# ShowMeShield.net
KiCad netlist of a schematic drawn in EAGLE
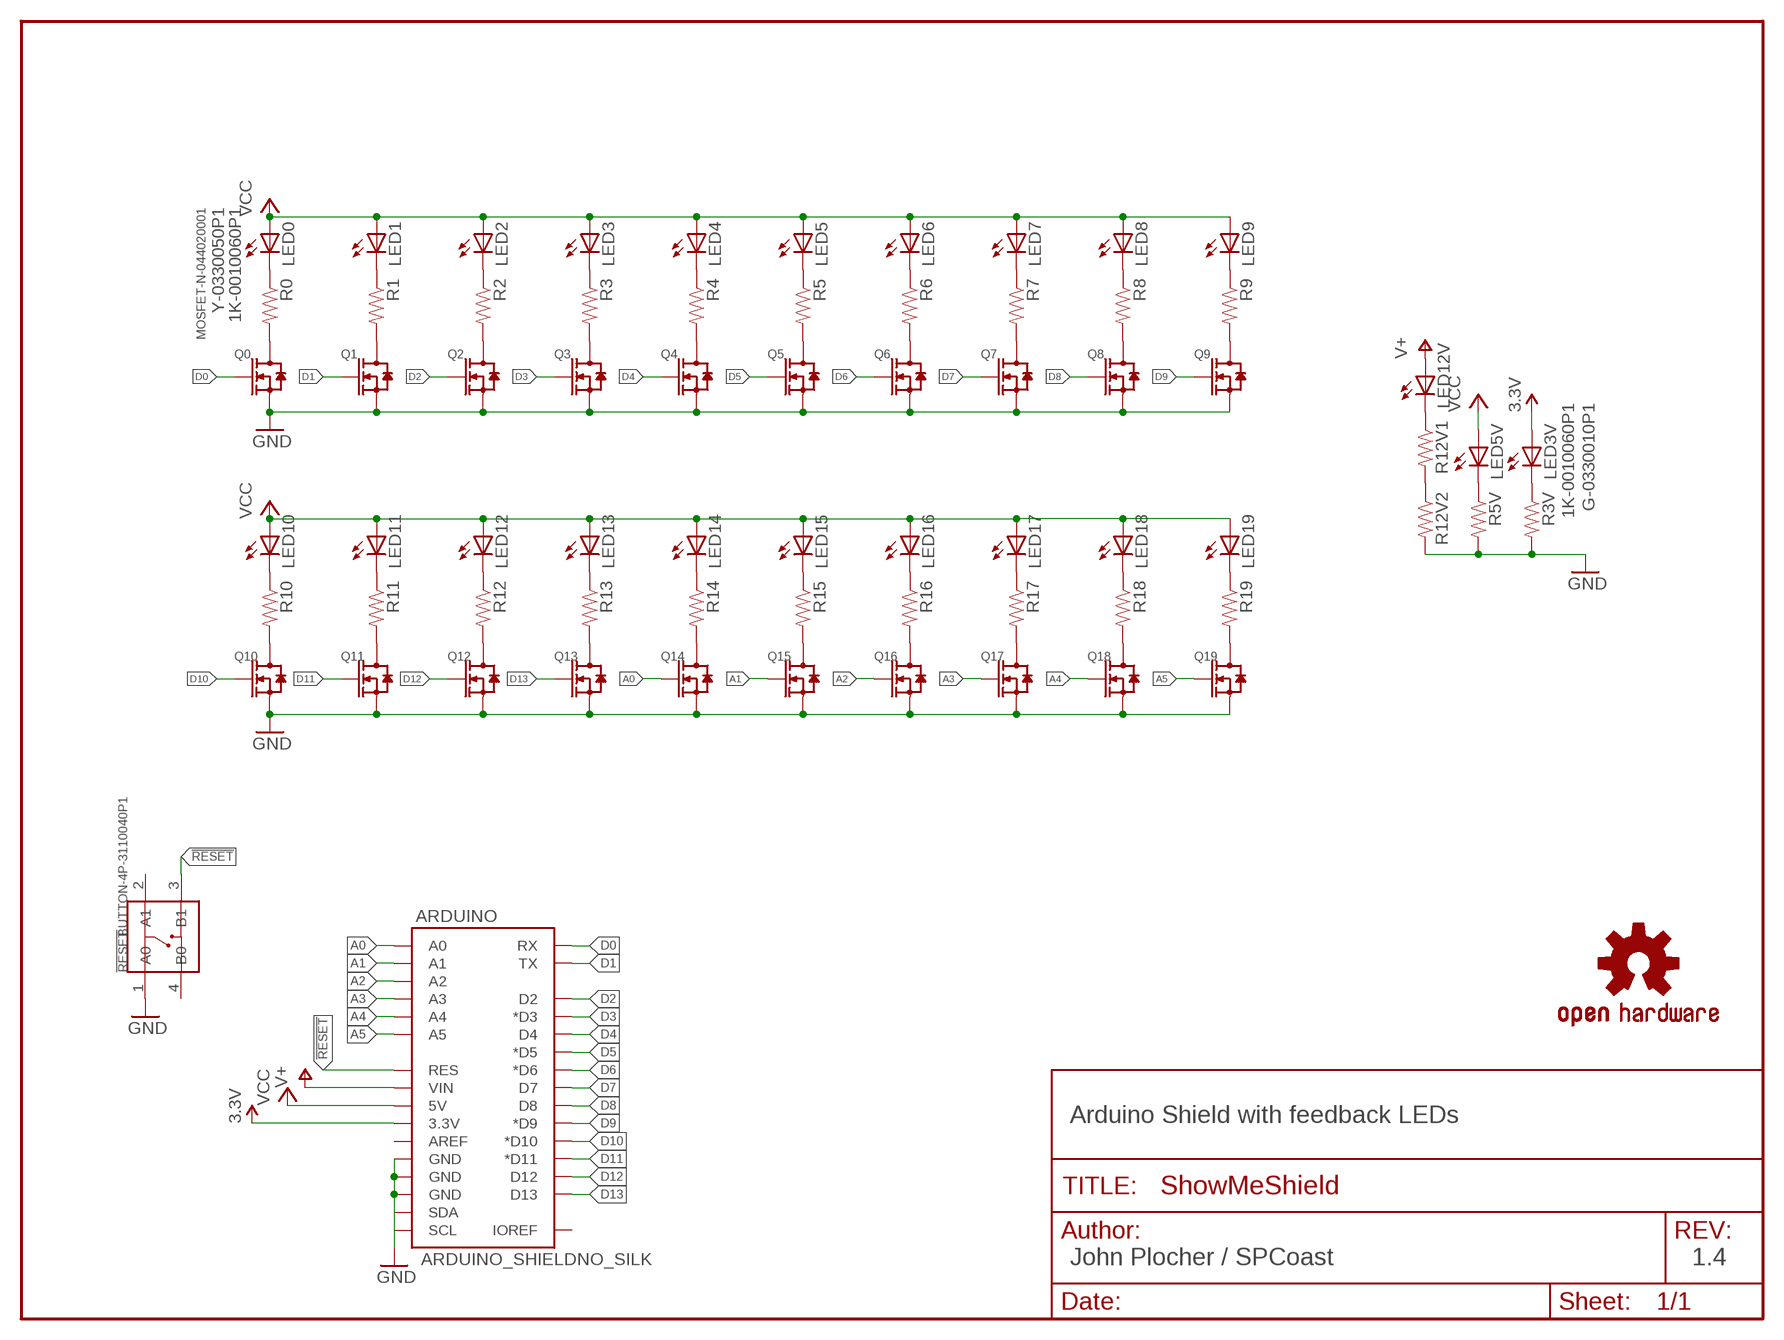
[diagram p0: schematic, sheet 1]

(export (version "E")
  (design (tool "Eeschema 10.0.6"))
  (components
    (comp (ref "!RESET")
      (value "BUTTON-4P-3110040P1")
      (footprint "eagle-import:4P-6.0X6.0X5.0H")
      (libsource (lib "eagle-import") (part "BUTTON-4P-3110040P1"))
    )
    (comp (ref "ARDUINO")
      (value "ARDUINO_SHIELDNO_SILK")
      (footprint "eagle-import:DUEMILANOVE_VIAS")
      (libsource (lib "eagle-import") (part "ARDUINO_SHIELDNO_SILK"))
    )
    (comp (ref "LED0")
      (value "Y-0330050P1")
      (footprint "eagle-import:CHIPLED_0603")
      (libsource (lib "eagle-import") (part "LEDCHIPLED_0603"))
    )
    (comp (ref "LED1")
      (value "Y-0330050P1")
      (footprint "eagle-import:CHIPLED_0603")
      (libsource (lib "eagle-import") (part "LEDCHIPLED_0603"))
    )
    (comp (ref "LED2")
      (value "Y-0330050P1")
      (footprint "eagle-import:CHIPLED_0603")
      (libsource (lib "eagle-import") (part "LEDCHIPLED_0603"))
    )
    (comp (ref "LED3")
      (value "Y-0330050P1")
      (footprint "eagle-import:CHIPLED_0603")
      (libsource (lib "eagle-import") (part "LEDCHIPLED_0603"))
    )
    (comp (ref "LED3V")
      (value "G-0330010P1")
      (footprint "eagle-import:CHIPLED_0603")
      (libsource (lib "eagle-import") (part "LEDCHIPLED_0603"))
    )
    (comp (ref "LED4")
      (value "Y-0330050P1")
      (footprint "eagle-import:CHIPLED_0603")
      (libsource (lib "eagle-import") (part "LEDCHIPLED_0603"))
    )
    (comp (ref "LED5")
      (value "Y-0330050P1")
      (footprint "eagle-import:CHIPLED_0603")
      (libsource (lib "eagle-import") (part "LEDCHIPLED_0603"))
    )
    (comp (ref "LED5V")
      (value "G-0330010P1")
      (footprint "eagle-import:CHIPLED_0603")
      (libsource (lib "eagle-import") (part "LEDCHIPLED_0603"))
    )
    (comp (ref "LED6")
      (value "Y-0330050P1")
      (footprint "eagle-import:CHIPLED_0603")
      (libsource (lib "eagle-import") (part "LEDCHIPLED_0603"))
    )
    (comp (ref "LED7")
      (value "Y-0330050P1")
      (footprint "eagle-import:CHIPLED_0603")
      (libsource (lib "eagle-import") (part "LEDCHIPLED_0603"))
    )
    (comp (ref "LED8")
      (value "Y-0330050P1")
      (footprint "eagle-import:CHIPLED_0603")
      (libsource (lib "eagle-import") (part "LEDCHIPLED_0603"))
    )
    (comp (ref "LED9")
      (value "Y-0330050P1")
      (footprint "eagle-import:CHIPLED_0603")
      (libsource (lib "eagle-import") (part "LEDCHIPLED_0603"))
    )
    (comp (ref "LED10")
      (value "Y-0330050P1")
      (footprint "eagle-import:CHIPLED_0603")
      (libsource (lib "eagle-import") (part "LEDCHIPLED_0603"))
    )
    (comp (ref "LED11")
      (value "Y-0330050P1")
      (footprint "eagle-import:CHIPLED_0603")
      (libsource (lib "eagle-import") (part "LEDCHIPLED_0603"))
    )
    (comp (ref "LED12")
      (value "Y-0330050P1")
      (footprint "eagle-import:CHIPLED_0603")
      (libsource (lib "eagle-import") (part "LEDCHIPLED_0603"))
    )
    (comp (ref "LED12V")
      (value "G-0330010P1")
      (footprint "eagle-import:CHIPLED_0603")
      (libsource (lib "eagle-import") (part "LEDCHIPLED_0603"))
    )
    (comp (ref "LED13")
      (value "Y-0330050P1")
      (footprint "eagle-import:CHIPLED_0603")
      (libsource (lib "eagle-import") (part "LEDCHIPLED_0603"))
    )
    (comp (ref "LED14")
      (value "Y-0330050P1")
      (footprint "eagle-import:CHIPLED_0603")
      (libsource (lib "eagle-import") (part "LEDCHIPLED_0603"))
    )
    (comp (ref "LED15")
      (value "Y-0330050P1")
      (footprint "eagle-import:CHIPLED_0603")
      (libsource (lib "eagle-import") (part "LEDCHIPLED_0603"))
    )
    (comp (ref "LED16")
      (value "Y-0330050P1")
      (footprint "eagle-import:CHIPLED_0603")
      (libsource (lib "eagle-import") (part "LEDCHIPLED_0603"))
    )
    (comp (ref "LED17")
      (value "Y-0330050P1")
      (footprint "eagle-import:CHIPLED_0603")
      (libsource (lib "eagle-import") (part "LEDCHIPLED_0603"))
    )
    (comp (ref "LED18")
      (value "Y-0330050P1")
      (footprint "eagle-import:CHIPLED_0603")
      (libsource (lib "eagle-import") (part "LEDCHIPLED_0603"))
    )
    (comp (ref "LED19")
      (value "Y-0330050P1")
      (footprint "eagle-import:CHIPLED_0603")
      (libsource (lib "eagle-import") (part "LEDCHIPLED_0603"))
    )
    (comp (ref "Q0")
      (value "MOSFET-N-044020001")
      (footprint "eagle-import:SOT23")
      (libsource (lib "eagle-import") (part "MOSFET-N-044020001"))
    )
    (comp (ref "Q1")
      (value "MOSFET-N-044020001")
      (footprint "eagle-import:SOT23")
      (libsource (lib "eagle-import") (part "MOSFET-N-044020001"))
    )
    (comp (ref "Q2")
      (value "MOSFET-N-044020001")
      (footprint "eagle-import:SOT23")
      (libsource (lib "eagle-import") (part "MOSFET-N-044020001"))
    )
    (comp (ref "Q3")
      (value "MOSFET-N-044020001")
      (footprint "eagle-import:SOT23")
      (libsource (lib "eagle-import") (part "MOSFET-N-044020001"))
    )
    (comp (ref "Q4")
      (value "MOSFET-N-044020001")
      (footprint "eagle-import:SOT23")
      (libsource (lib "eagle-import") (part "MOSFET-N-044020001"))
    )
    (comp (ref "Q5")
      (value "MOSFET-N-044020001")
      (footprint "eagle-import:SOT23")
      (libsource (lib "eagle-import") (part "MOSFET-N-044020001"))
    )
    (comp (ref "Q6")
      (value "MOSFET-N-044020001")
      (footprint "eagle-import:SOT23")
      (libsource (lib "eagle-import") (part "MOSFET-N-044020001"))
    )
    (comp (ref "Q7")
      (value "MOSFET-N-044020001")
      (footprint "eagle-import:SOT23")
      (libsource (lib "eagle-import") (part "MOSFET-N-044020001"))
    )
    (comp (ref "Q8")
      (value "MOSFET-N-044020001")
      (footprint "eagle-import:SOT23")
      (libsource (lib "eagle-import") (part "MOSFET-N-044020001"))
    )
    (comp (ref "Q9")
      (value "MOSFET-N-044020001")
      (footprint "eagle-import:SOT23")
      (libsource (lib "eagle-import") (part "MOSFET-N-044020001"))
    )
    (comp (ref "Q10")
      (value "MOSFET-N-044020001")
      (footprint "eagle-import:SOT23")
      (libsource (lib "eagle-import") (part "MOSFET-N-044020001"))
    )
    (comp (ref "Q11")
      (value "MOSFET-N-044020001")
      (footprint "eagle-import:SOT23")
      (libsource (lib "eagle-import") (part "MOSFET-N-044020001"))
    )
    (comp (ref "Q12")
      (value "MOSFET-N-044020001")
      (footprint "eagle-import:SOT23")
      (libsource (lib "eagle-import") (part "MOSFET-N-044020001"))
    )
    (comp (ref "Q13")
      (value "MOSFET-N-044020001")
      (footprint "eagle-import:SOT23")
      (libsource (lib "eagle-import") (part "MOSFET-N-044020001"))
    )
    (comp (ref "Q14")
      (value "MOSFET-N-044020001")
      (footprint "eagle-import:SOT23")
      (libsource (lib "eagle-import") (part "MOSFET-N-044020001"))
    )
    (comp (ref "Q15")
      (value "MOSFET-N-044020001")
      (footprint "eagle-import:SOT23")
      (libsource (lib "eagle-import") (part "MOSFET-N-044020001"))
    )
    (comp (ref "Q16")
      (value "MOSFET-N-044020001")
      (footprint "eagle-import:SOT23")
      (libsource (lib "eagle-import") (part "MOSFET-N-044020001"))
    )
    (comp (ref "Q17")
      (value "MOSFET-N-044020001")
      (footprint "eagle-import:SOT23")
      (libsource (lib "eagle-import") (part "MOSFET-N-044020001"))
    )
    (comp (ref "Q18")
      (value "MOSFET-N-044020001")
      (footprint "eagle-import:SOT23")
      (libsource (lib "eagle-import") (part "MOSFET-N-044020001"))
    )
    (comp (ref "Q19")
      (value "MOSFET-N-044020001")
      (footprint "eagle-import:SOT23")
      (libsource (lib "eagle-import") (part "MOSFET-N-044020001"))
    )
    (comp (ref "R0")
      (value "1K-0010060P1")
      (footprint "eagle-import:0603-RES")
      (libsource (lib "eagle-import") (part "RESISTOR0603-RES"))
    )
    (comp (ref "R1")
      (value "1K-0010060P1")
      (footprint "eagle-import:0603-RES")
      (libsource (lib "eagle-import") (part "RESISTOR0603-RES"))
    )
    (comp (ref "R2")
      (value "1K-0010060P1")
      (footprint "eagle-import:0603-RES")
      (libsource (lib "eagle-import") (part "RESISTOR0603-RES"))
    )
    (comp (ref "R3")
      (value "1K-0010060P1")
      (footprint "eagle-import:0603-RES")
      (libsource (lib "eagle-import") (part "RESISTOR0603-RES"))
    )
    (comp (ref "R3V")
      (value "1K-0010060P1")
      (footprint "eagle-import:0603-RES")
      (libsource (lib "eagle-import") (part "RESISTOR0603-RES"))
    )
    (comp (ref "R4")
      (value "1K-0010060P1")
      (footprint "eagle-import:0603-RES")
      (libsource (lib "eagle-import") (part "RESISTOR0603-RES"))
    )
    (comp (ref "R5")
      (value "1K-0010060P1")
      (footprint "eagle-import:0603-RES")
      (libsource (lib "eagle-import") (part "RESISTOR0603-RES"))
    )
    (comp (ref "R5V")
      (value "1K-0010060P1")
      (footprint "eagle-import:0603-RES")
      (libsource (lib "eagle-import") (part "RESISTOR0603-RES"))
    )
    (comp (ref "R6")
      (value "1K-0010060P1")
      (footprint "eagle-import:0603-RES")
      (libsource (lib "eagle-import") (part "RESISTOR0603-RES"))
    )
    (comp (ref "R7")
      (value "1K-0010060P1")
      (footprint "eagle-import:0603-RES")
      (libsource (lib "eagle-import") (part "RESISTOR0603-RES"))
    )
    (comp (ref "R8")
      (value "1K-0010060P1")
      (footprint "eagle-import:0603-RES")
      (libsource (lib "eagle-import") (part "RESISTOR0603-RES"))
    )
    (comp (ref "R9")
      (value "1K-0010060P1")
      (footprint "eagle-import:0603-RES")
      (libsource (lib "eagle-import") (part "RESISTOR0603-RES"))
    )
    (comp (ref "R10")
      (value "1K-0010060P1")
      (footprint "eagle-import:0603-RES")
      (libsource (lib "eagle-import") (part "RESISTOR0603-RES"))
    )
    (comp (ref "R11")
      (value "1K-0010060P1")
      (footprint "eagle-import:0603-RES")
      (libsource (lib "eagle-import") (part "RESISTOR0603-RES"))
    )
    (comp (ref "R12")
      (value "1K-0010060P1")
      (footprint "eagle-import:0603-RES")
      (libsource (lib "eagle-import") (part "RESISTOR0603-RES"))
    )
    (comp (ref "R12V1")
      (value "1K-0010060P1")
      (footprint "eagle-import:0603-RES")
      (libsource (lib "eagle-import") (part "RESISTOR0603-RES"))
    )
    (comp (ref "R12V2")
      (value "1K-0010060P1")
      (footprint "eagle-import:0603-RES")
      (libsource (lib "eagle-import") (part "RESISTOR0603-RES"))
    )
    (comp (ref "R13")
      (value "1K-0010060P1")
      (footprint "eagle-import:0603-RES")
      (libsource (lib "eagle-import") (part "RESISTOR0603-RES"))
    )
    (comp (ref "R14")
      (value "1K-0010060P1")
      (footprint "eagle-import:0603-RES")
      (libsource (lib "eagle-import") (part "RESISTOR0603-RES"))
    )
    (comp (ref "R15")
      (value "1K-0010060P1")
      (footprint "eagle-import:0603-RES")
      (libsource (lib "eagle-import") (part "RESISTOR0603-RES"))
    )
    (comp (ref "R16")
      (value "1K-0010060P1")
      (footprint "eagle-import:0603-RES")
      (libsource (lib "eagle-import") (part "RESISTOR0603-RES"))
    )
    (comp (ref "R17")
      (value "1K-0010060P1")
      (footprint "eagle-import:0603-RES")
      (libsource (lib "eagle-import") (part "RESISTOR0603-RES"))
    )
    (comp (ref "R18")
      (value "1K-0010060P1")
      (footprint "eagle-import:0603-RES")
      (libsource (lib "eagle-import") (part "RESISTOR0603-RES"))
    )
    (comp (ref "R19")
      (value "1K-0010060P1")
      (footprint "eagle-import:0603-RES")
      (libsource (lib "eagle-import") (part "RESISTOR0603-RES"))
    )
    (comp (ref "U$1")
      (value "OSHW-LOGOM")
      (footprint "eagle-import:OSHW-LOGO-M")
      (libsource (lib "eagle-import") (part "OSHW-LOGOM"))
    )
  )
  (nets
    (net (code "1") (name "/~{RESET}") (class "Default")
      (node (ref "!RESET") (pin "3") (pinfunction "B1_3") (pintype "bidirectional"))
      (node (ref "ARDUINO") (pin "RES") (pinfunction "RES_RES") (pintype "bidirectional"))
    )
    (net (code "2") (name "3.3V") (class "Default")
      (node (ref "ARDUINO") (pin "3.3V") (pinfunction "3.3V_3.3V") (pintype "bidirectional"))
      (node (ref "LED3V") (pin "A") (pinfunction "A_A") (pintype "passive"))
    )
    (net (code "3") (name "A0") (class "Default")
      (node (ref "ARDUINO") (pin "A0") (pinfunction "A0_A0") (pintype "bidirectional"))
      (node (ref "Q14") (pin "1") (pinfunction "G_1") (pintype "passive"))
    )
    (net (code "4") (name "A1") (class "Default")
      (node (ref "ARDUINO") (pin "A1") (pinfunction "A1_A1") (pintype "bidirectional"))
      (node (ref "Q15") (pin "1") (pinfunction "G_1") (pintype "passive"))
    )
    (net (code "5") (name "A2") (class "Default")
      (node (ref "ARDUINO") (pin "A2") (pinfunction "A2_A2") (pintype "bidirectional"))
      (node (ref "Q16") (pin "1") (pinfunction "G_1") (pintype "passive"))
    )
    (net (code "6") (name "A3") (class "Default")
      (node (ref "ARDUINO") (pin "A3") (pinfunction "A3_A3") (pintype "bidirectional"))
      (node (ref "Q17") (pin "1") (pinfunction "G_1") (pintype "passive"))
    )
    (net (code "7") (name "A4") (class "Default")
      (node (ref "ARDUINO") (pin "A4") (pinfunction "A4_A4") (pintype "bidirectional"))
      (node (ref "Q18") (pin "1") (pinfunction "G_1") (pintype "passive"))
    )
    (net (code "8") (name "A5") (class "Default")
      (node (ref "ARDUINO") (pin "A5") (pinfunction "A5_A5") (pintype "bidirectional"))
      (node (ref "Q19") (pin "1") (pinfunction "G_1") (pintype "passive"))
    )
    (net (code "9") (name "D0") (class "Default")
      (node (ref "ARDUINO") (pin "RX") (pinfunction "RX_RX") (pintype "bidirectional"))
      (node (ref "Q0") (pin "1") (pinfunction "G_1") (pintype "passive"))
    )
    (net (code "10") (name "D1") (class "Default")
      (node (ref "ARDUINO") (pin "TX") (pinfunction "TX_TX") (pintype "bidirectional"))
      (node (ref "Q1") (pin "1") (pinfunction "G_1") (pintype "passive"))
    )
    (net (code "11") (name "D2") (class "Default")
      (node (ref "ARDUINO") (pin "D2") (pinfunction "D2_D2") (pintype "bidirectional"))
      (node (ref "Q2") (pin "1") (pinfunction "G_1") (pintype "passive"))
    )
    (net (code "12") (name "D3") (class "Default")
      (node (ref "ARDUINO") (pin "D3") (pinfunction "*D3_D3") (pintype "bidirectional"))
      (node (ref "Q3") (pin "1") (pinfunction "G_1") (pintype "passive"))
    )
    (net (code "13") (name "D4") (class "Default")
      (node (ref "ARDUINO") (pin "D4") (pinfunction "D4_D4") (pintype "bidirectional"))
      (node (ref "Q4") (pin "1") (pinfunction "G_1") (pintype "passive"))
    )
    (net (code "14") (name "D5") (class "Default")
      (node (ref "ARDUINO") (pin "D5") (pinfunction "*D5_D5") (pintype "bidirectional"))
      (node (ref "Q5") (pin "1") (pinfunction "G_1") (pintype "passive"))
    )
    (net (code "15") (name "D6") (class "Default")
      (node (ref "ARDUINO") (pin "D6") (pinfunction "*D6_D6") (pintype "bidirectional"))
      (node (ref "Q6") (pin "1") (pinfunction "G_1") (pintype "passive"))
    )
    (net (code "16") (name "D7") (class "Default")
      (node (ref "ARDUINO") (pin "D7") (pinfunction "D7_D7") (pintype "bidirectional"))
      (node (ref "Q7") (pin "1") (pinfunction "G_1") (pintype "passive"))
    )
    (net (code "17") (name "D8") (class "Default")
      (node (ref "ARDUINO") (pin "D8") (pinfunction "D8_D8") (pintype "bidirectional"))
      (node (ref "Q8") (pin "1") (pinfunction "G_1") (pintype "passive"))
    )
    (net (code "18") (name "D9") (class "Default")
      (node (ref "ARDUINO") (pin "D9") (pinfunction "*D9_D9") (pintype "bidirectional"))
      (node (ref "Q9") (pin "1") (pinfunction "G_1") (pintype "passive"))
    )
    (net (code "19") (name "D10") (class "Default")
      (node (ref "ARDUINO") (pin "D10") (pinfunction "*D10_D10") (pintype "bidirectional"))
      (node (ref "Q10") (pin "1") (pinfunction "G_1") (pintype "passive"))
    )
    (net (code "20") (name "D11") (class "Default")
      (node (ref "ARDUINO") (pin "D11") (pinfunction "*D11_D11") (pintype "bidirectional"))
      (node (ref "Q11") (pin "1") (pinfunction "G_1") (pintype "passive"))
    )
    (net (code "21") (name "D12") (class "Default")
      (node (ref "ARDUINO") (pin "D12") (pinfunction "D12_D12") (pintype "bidirectional"))
      (node (ref "Q12") (pin "1") (pinfunction "G_1") (pintype "passive"))
    )
    (net (code "22") (name "D13") (class "Default")
      (node (ref "ARDUINO") (pin "D13") (pinfunction "D13_D13") (pintype "bidirectional"))
      (node (ref "Q13") (pin "1") (pinfunction "G_1") (pintype "passive"))
    )
    (net (code "23") (name "GND") (class "Default")
      (node (ref "!RESET") (pin "1") (pinfunction "A0_1") (pintype "bidirectional"))
      (node (ref "ARDUINO") (pin "GND@0") (pinfunction "GND_GND@0") (pintype "bidirectional"))
      (node (ref "ARDUINO") (pin "GND@1") (pinfunction "GND_GND@1") (pintype "bidirectional"))
      (node (ref "ARDUINO") (pin "GND@2") (pinfunction "GND_GND@2") (pintype "bidirectional"))
      (node (ref "Q0") (pin "2") (pinfunction "S_2") (pintype "passive"))
      (node (ref "Q1") (pin "2") (pinfunction "S_2") (pintype "passive"))
      (node (ref "Q10") (pin "2") (pinfunction "S_2") (pintype "passive"))
      (node (ref "Q11") (pin "2") (pinfunction "S_2") (pintype "passive"))
      (node (ref "Q12") (pin "2") (pinfunction "S_2") (pintype "passive"))
      (node (ref "Q13") (pin "2") (pinfunction "S_2") (pintype "passive"))
      (node (ref "Q14") (pin "2") (pinfunction "S_2") (pintype "passive"))
      (node (ref "Q15") (pin "2") (pinfunction "S_2") (pintype "passive"))
      (node (ref "Q16") (pin "2") (pinfunction "S_2") (pintype "passive"))
      (node (ref "Q17") (pin "2") (pinfunction "S_2") (pintype "passive"))
      (node (ref "Q18") (pin "2") (pinfunction "S_2") (pintype "passive"))
      (node (ref "Q19") (pin "2") (pinfunction "S_2") (pintype "passive"))
      (node (ref "Q2") (pin "2") (pinfunction "S_2") (pintype "passive"))
      (node (ref "Q3") (pin "2") (pinfunction "S_2") (pintype "passive"))
      (node (ref "Q4") (pin "2") (pinfunction "S_2") (pintype "passive"))
      (node (ref "Q5") (pin "2") (pinfunction "S_2") (pintype "passive"))
      (node (ref "Q6") (pin "2") (pinfunction "S_2") (pintype "passive"))
      (node (ref "Q7") (pin "2") (pinfunction "S_2") (pintype "passive"))
      (node (ref "Q8") (pin "2") (pinfunction "S_2") (pintype "passive"))
      (node (ref "Q9") (pin "2") (pinfunction "S_2") (pintype "passive"))
      (node (ref "R12V2") (pin "2") (pinfunction "2_2") (pintype "passive"))
      (node (ref "R3V") (pin "2") (pinfunction "2_2") (pintype "passive"))
      (node (ref "R5V") (pin "2") (pinfunction "2_2") (pintype "passive"))
    )
    (net (code "24") (name "Net-(LED0-PadC)") (class "Default")
      (node (ref "LED0") (pin "C") (pinfunction "C_C") (pintype "passive"))
      (node (ref "R0") (pin "1") (pinfunction "1_1") (pintype "passive"))
    )
    (net (code "25") (name "Net-(LED1-PadC)") (class "Default")
      (node (ref "LED1") (pin "C") (pinfunction "C_C") (pintype "passive"))
      (node (ref "R1") (pin "1") (pinfunction "1_1") (pintype "passive"))
    )
    (net (code "26") (name "Net-(LED2-PadC)") (class "Default")
      (node (ref "LED2") (pin "C") (pinfunction "C_C") (pintype "passive"))
      (node (ref "R2") (pin "1") (pinfunction "1_1") (pintype "passive"))
    )
    (net (code "27") (name "Net-(LED3-PadC)") (class "Default")
      (node (ref "LED3") (pin "C") (pinfunction "C_C") (pintype "passive"))
      (node (ref "R3") (pin "1") (pinfunction "1_1") (pintype "passive"))
    )
    (net (code "28") (name "Net-(LED3V-PadC)") (class "Default")
      (node (ref "LED3V") (pin "C") (pinfunction "C_C") (pintype "passive"))
      (node (ref "R3V") (pin "1") (pinfunction "1_1") (pintype "passive"))
    )
    (net (code "29") (name "Net-(LED4-PadC)") (class "Default")
      (node (ref "LED4") (pin "C") (pinfunction "C_C") (pintype "passive"))
      (node (ref "R4") (pin "1") (pinfunction "1_1") (pintype "passive"))
    )
    (net (code "30") (name "Net-(LED5-PadC)") (class "Default")
      (node (ref "LED5") (pin "C") (pinfunction "C_C") (pintype "passive"))
      (node (ref "R5") (pin "1") (pinfunction "1_1") (pintype "passive"))
    )
    (net (code "31") (name "Net-(LED5V-PadC)") (class "Default")
      (node (ref "LED5V") (pin "C") (pinfunction "C_C") (pintype "passive"))
      (node (ref "R5V") (pin "1") (pinfunction "1_1") (pintype "passive"))
    )
    (net (code "32") (name "Net-(LED6-PadC)") (class "Default")
      (node (ref "LED6") (pin "C") (pinfunction "C_C") (pintype "passive"))
      (node (ref "R6") (pin "1") (pinfunction "1_1") (pintype "passive"))
    )
    (net (code "33") (name "Net-(LED7-PadC)") (class "Default")
      (node (ref "LED7") (pin "C") (pinfunction "C_C") (pintype "passive"))
      (node (ref "R7") (pin "1") (pinfunction "1_1") (pintype "passive"))
    )
    (net (code "34") (name "Net-(LED8-PadC)") (class "Default")
      (node (ref "LED8") (pin "C") (pinfunction "C_C") (pintype "passive"))
      (node (ref "R8") (pin "1") (pinfunction "1_1") (pintype "passive"))
    )
    (net (code "35") (name "Net-(LED9-PadC)") (class "Default")
      (node (ref "LED9") (pin "C") (pinfunction "C_C") (pintype "passive"))
      (node (ref "R9") (pin "1") (pinfunction "1_1") (pintype "passive"))
    )
    (net (code "36") (name "Net-(LED10-PadC)") (class "Default")
      (node (ref "LED10") (pin "C") (pinfunction "C_C") (pintype "passive"))
      (node (ref "R10") (pin "1") (pinfunction "1_1") (pintype "passive"))
    )
    (net (code "37") (name "Net-(LED11-PadC)") (class "Default")
      (node (ref "LED11") (pin "C") (pinfunction "C_C") (pintype "passive"))
      (node (ref "R11") (pin "1") (pinfunction "1_1") (pintype "passive"))
    )
    (net (code "38") (name "Net-(LED12-PadC)") (class "Default")
      (node (ref "LED12") (pin "C") (pinfunction "C_C") (pintype "passive"))
      (node (ref "R12") (pin "1") (pinfunction "1_1") (pintype "passive"))
    )
    (net (code "39") (name "Net-(LED12V-PadC)") (class "Default")
      (node (ref "LED12V") (pin "C") (pinfunction "C_C") (pintype "passive"))
      (node (ref "R12V1") (pin "1") (pinfunction "1_1") (pintype "passive"))
    )
    (net (code "40") (name "Net-(LED13-PadC)") (class "Default")
      (node (ref "LED13") (pin "C") (pinfunction "C_C") (pintype "passive"))
      (node (ref "R13") (pin "1") (pinfunction "1_1") (pintype "passive"))
    )
    (net (code "41") (name "Net-(LED14-PadC)") (class "Default")
      (node (ref "LED14") (pin "C") (pinfunction "C_C") (pintype "passive"))
      (node (ref "R14") (pin "1") (pinfunction "1_1") (pintype "passive"))
    )
    (net (code "42") (name "Net-(LED15-PadC)") (class "Default")
      (node (ref "LED15") (pin "C") (pinfunction "C_C") (pintype "passive"))
      (node (ref "R15") (pin "1") (pinfunction "1_1") (pintype "passive"))
    )
    (net (code "43") (name "Net-(LED16-PadC)") (class "Default")
      (node (ref "LED16") (pin "C") (pinfunction "C_C") (pintype "passive"))
      (node (ref "R16") (pin "1") (pinfunction "1_1") (pintype "passive"))
    )
    (net (code "44") (name "Net-(LED17-PadC)") (class "Default")
      (node (ref "LED17") (pin "C") (pinfunction "C_C") (pintype "passive"))
      (node (ref "R17") (pin "1") (pinfunction "1_1") (pintype "passive"))
    )
    (net (code "45") (name "Net-(LED18-PadC)") (class "Default")
      (node (ref "LED18") (pin "C") (pinfunction "C_C") (pintype "passive"))
      (node (ref "R18") (pin "1") (pinfunction "1_1") (pintype "passive"))
    )
    (net (code "46") (name "Net-(LED19-PadC)") (class "Default")
      (node (ref "LED19") (pin "C") (pinfunction "C_C") (pintype "passive"))
      (node (ref "R19") (pin "1") (pinfunction "1_1") (pintype "passive"))
    )
    (net (code "47") (name "Net-(Q0-D)") (class "Default")
      (node (ref "Q0") (pin "3") (pinfunction "D_3") (pintype "passive"))
      (node (ref "R0") (pin "2") (pinfunction "2_2") (pintype "passive"))
    )
    (net (code "48") (name "Net-(Q1-D)") (class "Default")
      (node (ref "Q1") (pin "3") (pinfunction "D_3") (pintype "passive"))
      (node (ref "R1") (pin "2") (pinfunction "2_2") (pintype "passive"))
    )
    (net (code "49") (name "Net-(Q2-D)") (class "Default")
      (node (ref "Q2") (pin "3") (pinfunction "D_3") (pintype "passive"))
      (node (ref "R2") (pin "2") (pinfunction "2_2") (pintype "passive"))
    )
    (net (code "50") (name "Net-(Q3-D)") (class "Default")
      (node (ref "Q3") (pin "3") (pinfunction "D_3") (pintype "passive"))
      (node (ref "R3") (pin "2") (pinfunction "2_2") (pintype "passive"))
    )
    (net (code "51") (name "Net-(Q4-D)") (class "Default")
      (node (ref "Q4") (pin "3") (pinfunction "D_3") (pintype "passive"))
      (node (ref "R4") (pin "2") (pinfunction "2_2") (pintype "passive"))
    )
    (net (code "52") (name "Net-(Q5-D)") (class "Default")
      (node (ref "Q5") (pin "3") (pinfunction "D_3") (pintype "passive"))
      (node (ref "R5") (pin "2") (pinfunction "2_2") (pintype "passive"))
    )
    (net (code "53") (name "Net-(Q6-D)") (class "Default")
      (node (ref "Q6") (pin "3") (pinfunction "D_3") (pintype "passive"))
      (node (ref "R6") (pin "2") (pinfunction "2_2") (pintype "passive"))
    )
    (net (code "54") (name "Net-(Q7-D)") (class "Default")
      (node (ref "Q7") (pin "3") (pinfunction "D_3") (pintype "passive"))
      (node (ref "R7") (pin "2") (pinfunction "2_2") (pintype "passive"))
    )
    (net (code "55") (name "Net-(Q8-D)") (class "Default")
      (node (ref "Q8") (pin "3") (pinfunction "D_3") (pintype "passive"))
      (node (ref "R8") (pin "2") (pinfunction "2_2") (pintype "passive"))
    )
    (net (code "56") (name "Net-(Q9-D)") (class "Default")
      (node (ref "Q9") (pin "3") (pinfunction "D_3") (pintype "passive"))
      (node (ref "R9") (pin "2") (pinfunction "2_2") (pintype "passive"))
    )
    (net (code "57") (name "Net-(Q10-D)") (class "Default")
      (node (ref "Q10") (pin "3") (pinfunction "D_3") (pintype "passive"))
      (node (ref "R10") (pin "2") (pinfunction "2_2") (pintype "passive"))
    )
    (net (code "58") (name "Net-(Q11-D)") (class "Default")
      (node (ref "Q11") (pin "3") (pinfunction "D_3") (pintype "passive"))
      (node (ref "R11") (pin "2") (pinfunction "2_2") (pintype "passive"))
    )
    (net (code "59") (name "Net-(Q12-D)") (class "Default")
      (node (ref "Q12") (pin "3") (pinfunction "D_3") (pintype "passive"))
      (node (ref "R12") (pin "2") (pinfunction "2_2") (pintype "passive"))
    )
    (net (code "60") (name "Net-(Q13-D)") (class "Default")
      (node (ref "Q13") (pin "3") (pinfunction "D_3") (pintype "passive"))
      (node (ref "R13") (pin "2") (pinfunction "2_2") (pintype "passive"))
    )
    (net (code "61") (name "Net-(Q14-D)") (class "Default")
      (node (ref "Q14") (pin "3") (pinfunction "D_3") (pintype "passive"))
      (node (ref "R14") (pin "2") (pinfunction "2_2") (pintype "passive"))
    )
    (net (code "62") (name "Net-(Q15-D)") (class "Default")
      (node (ref "Q15") (pin "3") (pinfunction "D_3") (pintype "passive"))
      (node (ref "R15") (pin "2") (pinfunction "2_2") (pintype "passive"))
    )
    (net (code "63") (name "Net-(Q16-D)") (class "Default")
      (node (ref "Q16") (pin "3") (pinfunction "D_3") (pintype "passive"))
      (node (ref "R16") (pin "2") (pinfunction "2_2") (pintype "passive"))
    )
    (net (code "64") (name "Net-(Q17-D)") (class "Default")
      (node (ref "Q17") (pin "3") (pinfunction "D_3") (pintype "passive"))
      (node (ref "R17") (pin "2") (pinfunction "2_2") (pintype "passive"))
    )
    (net (code "65") (name "Net-(Q18-D)") (class "Default")
      (node (ref "Q18") (pin "3") (pinfunction "D_3") (pintype "passive"))
      (node (ref "R18") (pin "2") (pinfunction "2_2") (pintype "passive"))
    )
    (net (code "66") (name "Net-(Q19-D)") (class "Default")
      (node (ref "Q19") (pin "3") (pinfunction "D_3") (pintype "passive"))
      (node (ref "R19") (pin "2") (pinfunction "2_2") (pintype "passive"))
    )
    (net (code "67") (name "Net-(R12V1-Pad2)") (class "Default")
      (node (ref "R12V1") (pin "2") (pinfunction "2_2") (pintype "passive"))
      (node (ref "R12V2") (pin "1") (pinfunction "1_1") (pintype "passive"))
    )
    (net (code "68") (name "V+") (class "Default")
      (node (ref "ARDUINO") (pin "VIN") (pinfunction "VIN_VIN") (pintype "bidirectional"))
      (node (ref "LED12V") (pin "A") (pinfunction "A_A") (pintype "passive"))
    )
    (net (code "69") (name "VCC") (class "Default")
      (node (ref "ARDUINO") (pin "5V") (pinfunction "5V_5V") (pintype "bidirectional"))
      (node (ref "LED0") (pin "A") (pinfunction "A_A") (pintype "passive"))
      (node (ref "LED1") (pin "A") (pinfunction "A_A") (pintype "passive"))
      (node (ref "LED10") (pin "A") (pinfunction "A_A") (pintype "passive"))
      (node (ref "LED11") (pin "A") (pinfunction "A_A") (pintype "passive"))
      (node (ref "LED12") (pin "A") (pinfunction "A_A") (pintype "passive"))
      (node (ref "LED13") (pin "A") (pinfunction "A_A") (pintype "passive"))
      (node (ref "LED14") (pin "A") (pinfunction "A_A") (pintype "passive"))
      (node (ref "LED15") (pin "A") (pinfunction "A_A") (pintype "passive"))
      (node (ref "LED16") (pin "A") (pinfunction "A_A") (pintype "passive"))
      (node (ref "LED17") (pin "A") (pinfunction "A_A") (pintype "passive"))
      (node (ref "LED18") (pin "A") (pinfunction "A_A") (pintype "passive"))
      (node (ref "LED19") (pin "A") (pinfunction "A_A") (pintype "passive"))
      (node (ref "LED2") (pin "A") (pinfunction "A_A") (pintype "passive"))
      (node (ref "LED3") (pin "A") (pinfunction "A_A") (pintype "passive"))
      (node (ref "LED4") (pin "A") (pinfunction "A_A") (pintype "passive"))
      (node (ref "LED5") (pin "A") (pinfunction "A_A") (pintype "passive"))
      (node (ref "LED5V") (pin "A") (pinfunction "A_A") (pintype "passive"))
      (node (ref "LED6") (pin "A") (pinfunction "A_A") (pintype "passive"))
      (node (ref "LED7") (pin "A") (pinfunction "A_A") (pintype "passive"))
      (node (ref "LED8") (pin "A") (pinfunction "A_A") (pintype "passive"))
      (node (ref "LED9") (pin "A") (pinfunction "A_A") (pintype "passive"))
    )
    (net (code "70") (name "unconnected-(!RESET-A1-Pad2)") (class "Default")
      (node (ref "!RESET") (pin "2") (pinfunction "A1_2") (pintype "bidirectional"))
    )
    (net (code "71") (name "unconnected-(!RESET-B0-Pad4)") (class "Default")
      (node (ref "!RESET") (pin "4") (pinfunction "B0_4") (pintype "bidirectional"))
    )
    (net (code "72") (name "unconnected-(ARDUINO-PadAREF)") (class "Default")
      (node (ref "ARDUINO") (pin "AREF") (pinfunction "AREF_AREF") (pintype "bidirectional"))
    )
    (net (code "73") (name "unconnected-(ARDUINO-PadIOREF)") (class "Default")
      (node (ref "ARDUINO") (pin "IOREF") (pinfunction "IOREF_IOREF") (pintype "bidirectional"))
    )
    (net (code "74") (name "unconnected-(ARDUINO-PadSCL)") (class "Default")
      (node (ref "ARDUINO") (pin "SCL") (pinfunction "SCL_SCL") (pintype "bidirectional"))
    )
    (net (code "75") (name "unconnected-(ARDUINO-PadSDA)") (class "Default")
      (node (ref "ARDUINO") (pin "SDA") (pinfunction "SDA_SDA") (pintype "bidirectional"))
    )
  )
)
